# Main.net
KiCad netlist of a schematic drawn in EAGLE
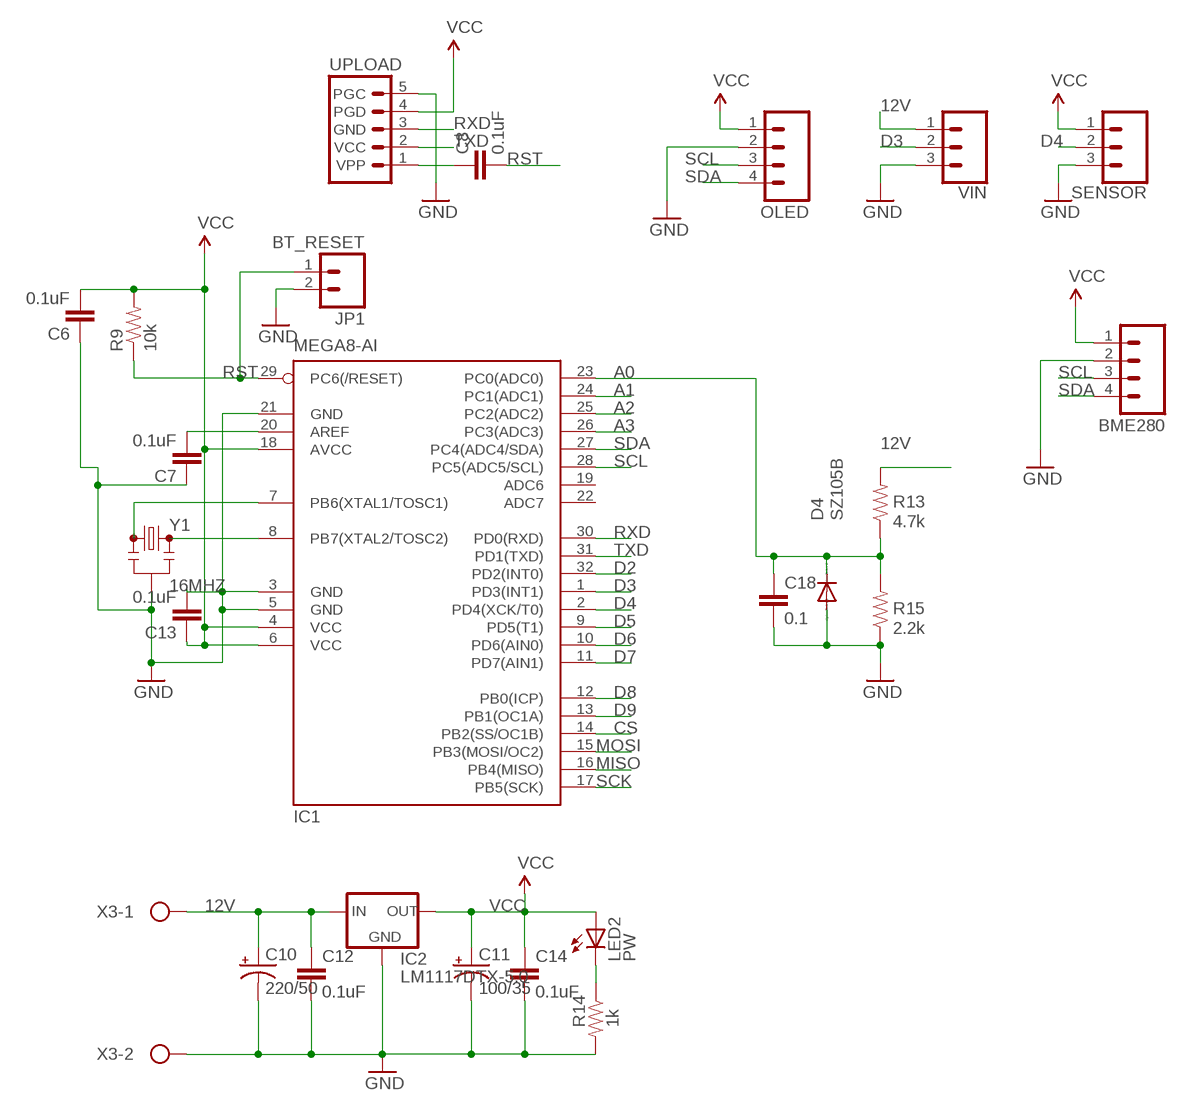
[diagram p0: schematic, sheet 1]

(export (version "E")
  (design (tool "Eeschema 10.0.6"))
  (components
    (comp (ref "BME280")
      (value "M04PTH")
      (footprint "eagle-import:1X04")
      (libsource (lib "eagle-import") (part "M04PTH"))
    )
    (comp (ref "C6")
      (value "0.1uF")
      (footprint "eagle-import:0805")
      (libsource (lib "eagle-import") (part "CAP0805"))
    )
    (comp (ref "C7")
      (value "0.1uF")
      (footprint "eagle-import:0805")
      (libsource (lib "eagle-import") (part "CAP0805"))
    )
    (comp (ref "C8")
      (value "0.1uF")
      (footprint "eagle-import:0805")
      (libsource (lib "eagle-import") (part "CAP0805"))
    )
    (comp (ref "C10")
      (value "220/50")
      (footprint "eagle-import:153CLV-1010")
      (libsource (lib "eagle-import") (part "CPOL-US153CLV-1010"))
    )
    (comp (ref "C11")
      (value "100/35")
      (footprint "eagle-import:153CLV-0605")
      (libsource (lib "eagle-import") (part "CPOL-US153CLV-0605"))
    )
    (comp (ref "C12")
      (value "0.1uF")
      (footprint "eagle-import:0805")
      (libsource (lib "eagle-import") (part "CAP0805"))
    )
    (comp (ref "C13")
      (value "0.1uF")
      (footprint "eagle-import:0805")
      (libsource (lib "eagle-import") (part "CAP0805"))
    )
    (comp (ref "C14")
      (value "0.1uF")
      (footprint "eagle-import:0805")
      (libsource (lib "eagle-import") (part "CAP0805"))
    )
    (comp (ref "C18")
      (value "0.1")
      (footprint "eagle-import:0805")
      (libsource (lib "eagle-import") (part "CAP0805"))
    )
    (comp (ref "D4")
      (value "SZ105B")
      (footprint "eagle-import:DO-214AC")
      (libsource (lib "eagle-import") (part "DIODE-DO-214AC"))
    )
    (comp (ref "IC1")
      (value "MEGA8-AI")
      (footprint "eagle-import:TQFP32-08")
      (fields (field (name "MPN") "ATMEGA8-16AU"))
      (libsource (lib "eagle-import") (part "MEGA8-AI"))
    )
    (comp (ref "IC2")
      (value "LM1117DTX-5.0")
      (footprint "eagle-import:TO252")
      (libsource (lib "eagle-import") (part "LM1117DTX-3.3"))
    )
    (comp (ref "JP1")
      (value "BT_RESET")
      (footprint "eagle-import:1X02")
      (libsource (lib "eagle-import") (part "M02PTH"))
    )
    (comp (ref "LED2")
      (value "PW")
      (footprint "eagle-import:LED3MM")
      (libsource (lib "eagle-import") (part "LED3MM"))
    )
    (comp (ref "OLED")
      (value "M04PTH")
      (footprint "eagle-import:1X04")
      (libsource (lib "eagle-import") (part "M04PTH"))
    )
    (comp (ref "R9")
      (value "10k")
      (footprint "eagle-import:0805")
      (libsource (lib "eagle-import") (part "RESISTOR0805-RES"))
    )
    (comp (ref "R13")
      (value "4.7k")
      (footprint "eagle-import:0805")
      (libsource (lib "eagle-import") (part "RESISTOR0805-RES"))
    )
    (comp (ref "R14")
      (value "1k")
      (footprint "eagle-import:0805")
      (libsource (lib "eagle-import") (part "RESISTOR0805-RES"))
    )
    (comp (ref "R15")
      (value "2.2k")
      (footprint "eagle-import:0805")
      (libsource (lib "eagle-import") (part "RESISTOR0805-RES"))
    )
    (comp (ref "SENSOR")
      (value "CONN_03JST-PTH-VERT")
      (footprint "eagle-import:JST-3-PTH-VERT")
      (libsource (lib "eagle-import") (part "CONN_03JST-PTH-VERT"))
    )
    (comp (ref "UPLOAD")
      (value "PIC_ICSP_MINI_5_PIN")
      (footprint "eagle-import:PIC_ICSP_MINI_5_PIN")
      (libsource (lib "eagle-import") (part "PIC_ICSP_MINI_5_PIN"))
    )
    (comp (ref "VIN")
      (value "CONN_03JST-PTH-VERT")
      (footprint "eagle-import:JST-3-PTH-VERT")
      (libsource (lib "eagle-import") (part "CONN_03JST-PTH-VERT"))
    )
    (comp (ref "X3")
      (value "RELAY1")
      (footprint "eagle-import:W237-102")
      (fields (field (name "MPN") "237-102"))
      (libsource (lib "eagle-import") (part "W237-102"))
    )
    (comp (ref "Y1")
      (value "16MHZ")
      (footprint "eagle-import:RESONATOR-SMD")
      (libsource (lib "eagle-import") (part "RESONATOR16MHZ"))
    )
  )
  (nets
    (net (code "1") (name "/12V") (class "Default")
      (node (ref "C10") (pin "+") (pinfunction "+_+") (pintype "passive"))
      (node (ref "C12") (pin "1") (pinfunction "1_1") (pintype "passive"))
      (node (ref "IC2") (pin "2") (pinfunction "IN_2") (pintype "input"))
      (node (ref "R13") (pin "2") (pinfunction "2_2") (pintype "passive"))
      (node (ref "VIN") (pin "1") (pinfunction "1_1") (pintype "passive"))
      (node (ref "X3") (pin "1") (pinfunction "KL_1") (pintype "passive"))
    )
    (net (code "2") (name "/A0") (class "Default")
      (node (ref "C18") (pin "1") (pinfunction "1_1") (pintype "passive"))
      (node (ref "D4") (pin "C") (pinfunction "C_C") (pintype "passive"))
      (node (ref "IC1") (pin "23") (pinfunction "PC0(ADC0)_23") (pintype "bidirectional"))
      (node (ref "R13") (pin "1") (pinfunction "1_1") (pintype "passive"))
      (node (ref "R15") (pin "2") (pinfunction "2_2") (pintype "passive"))
    )
    (net (code "3") (name "/A1") (class "Default")
      (node (ref "IC1") (pin "24") (pinfunction "PC1(ADC1)_24") (pintype "bidirectional"))
    )
    (net (code "4") (name "/A2") (class "Default")
      (node (ref "IC1") (pin "25") (pinfunction "PC2(ADC2)_25") (pintype "bidirectional"))
    )
    (net (code "5") (name "/A3") (class "Default")
      (node (ref "IC1") (pin "26") (pinfunction "PC3(ADC3)_26") (pintype "bidirectional"))
    )
    (net (code "6") (name "/CS") (class "Default")
      (node (ref "IC1") (pin "14") (pinfunction "PB2(SS/OC1B)_14") (pintype "bidirectional"))
    )
    (net (code "7") (name "/D2") (class "Default")
      (node (ref "IC1") (pin "32") (pinfunction "PD2(INT0)_32") (pintype "bidirectional"))
    )
    (net (code "8") (name "/D3") (class "Default")
      (node (ref "IC1") (pin "1") (pinfunction "PD3(INT1)_1") (pintype "bidirectional"))
      (node (ref "VIN") (pin "2") (pinfunction "2_2") (pintype "passive"))
    )
    (net (code "9") (name "/D4") (class "Default")
      (node (ref "IC1") (pin "2") (pinfunction "PD4(XCK/T0)_2") (pintype "bidirectional"))
      (node (ref "SENSOR") (pin "2") (pinfunction "2_2") (pintype "passive"))
    )
    (net (code "10") (name "/D5") (class "Default")
      (node (ref "IC1") (pin "9") (pinfunction "PD5(T1)_9") (pintype "bidirectional"))
    )
    (net (code "11") (name "/D6") (class "Default")
      (node (ref "IC1") (pin "10") (pinfunction "PD6(AIN0)_10") (pintype "bidirectional"))
    )
    (net (code "12") (name "/D7") (class "Default")
      (node (ref "IC1") (pin "11") (pinfunction "PD7(AIN1)_11") (pintype "bidirectional"))
    )
    (net (code "13") (name "/D8") (class "Default")
      (node (ref "IC1") (pin "12") (pinfunction "PB0(ICP)_12") (pintype "bidirectional"))
    )
    (net (code "14") (name "/D9") (class "Default")
      (node (ref "IC1") (pin "13") (pinfunction "PB1(OC1A)_13") (pintype "bidirectional"))
    )
    (net (code "15") (name "/MISO") (class "Default")
      (node (ref "IC1") (pin "16") (pinfunction "PB4(MISO)_16") (pintype "bidirectional"))
    )
    (net (code "16") (name "/MOSI") (class "Default")
      (node (ref "IC1") (pin "15") (pinfunction "PB3(MOSI/OC2)_15") (pintype "bidirectional"))
    )
    (net (code "17") (name "/RST") (class "Default")
      (node (ref "C8") (pin "2") (pinfunction "2_2") (pintype "passive"))
      (node (ref "IC1") (pin "29") (pinfunction "PC6(/RESET)_29") (pintype "bidirectional"))
      (node (ref "JP1") (pin "1") (pinfunction "1_1") (pintype "passive"))
      (node (ref "R9") (pin "1") (pinfunction "1_1") (pintype "passive"))
    )
    (net (code "18") (name "/RXD") (class "Default")
      (node (ref "IC1") (pin "30") (pinfunction "PD0(RXD)_30") (pintype "bidirectional"))
      (node (ref "UPLOAD") (pin "3") (pinfunction "GND_3") (pintype "passive"))
    )
    (net (code "19") (name "/SCK") (class "Default")
      (node (ref "IC1") (pin "17") (pinfunction "PB5(SCK)_17") (pintype "bidirectional"))
    )
    (net (code "20") (name "/SCL") (class "Default")
      (node (ref "BME280") (pin "3") (pinfunction "3_3") (pintype "passive"))
      (node (ref "IC1") (pin "28") (pinfunction "PC5(ADC5/SCL)_28") (pintype "bidirectional"))
      (node (ref "OLED") (pin "3") (pinfunction "3_3") (pintype "passive"))
    )
    (net (code "21") (name "/SDA") (class "Default")
      (node (ref "BME280") (pin "4") (pinfunction "4_4") (pintype "passive"))
      (node (ref "IC1") (pin "27") (pinfunction "PC4(ADC4/SDA)_27") (pintype "bidirectional"))
      (node (ref "OLED") (pin "4") (pinfunction "4_4") (pintype "passive"))
    )
    (net (code "22") (name "/TXD") (class "Default")
      (node (ref "IC1") (pin "31") (pinfunction "PD1(TXD)_31") (pintype "bidirectional"))
      (node (ref "UPLOAD") (pin "2") (pinfunction "VCC_2") (pintype "passive"))
    )
    (net (code "23") (name "GND") (class "Default")
      (node (ref "BME280") (pin "2") (pinfunction "2_2") (pintype "passive"))
      (node (ref "C10") (pin "-") (pinfunction "-_-") (pintype "passive"))
      (node (ref "C11") (pin "-") (pinfunction "-_-") (pintype "passive"))
      (node (ref "C12") (pin "2") (pinfunction "2_2") (pintype "passive"))
      (node (ref "C13") (pin "2") (pinfunction "2_2") (pintype "passive"))
      (node (ref "C14") (pin "2") (pinfunction "2_2") (pintype "passive"))
      (node (ref "C18") (pin "2") (pinfunction "2_2") (pintype "passive"))
      (node (ref "C6") (pin "1") (pinfunction "1_1") (pintype "passive"))
      (node (ref "C7") (pin "1") (pinfunction "1_1") (pintype "passive"))
      (node (ref "D4") (pin "A") (pinfunction "A_A") (pintype "passive"))
      (node (ref "IC1") (pin "21") (pinfunction "GND_21") (pintype "power_in"))
      (node (ref "IC1") (pin "3") (pinfunction "GND_3") (pintype "power_in"))
      (node (ref "IC1") (pin "5") (pinfunction "GND_5") (pintype "power_in"))
      (node (ref "IC2") (pin "1") (pinfunction "GND_1") (pintype "input"))
      (node (ref "JP1") (pin "2") (pinfunction "2_2") (pintype "passive"))
      (node (ref "OLED") (pin "2") (pinfunction "2_2") (pintype "passive"))
      (node (ref "R14") (pin "2") (pinfunction "2_2") (pintype "passive"))
      (node (ref "R15") (pin "1") (pinfunction "1_1") (pintype "passive"))
      (node (ref "SENSOR") (pin "3") (pinfunction "3_3") (pintype "passive"))
      (node (ref "UPLOAD") (pin "5") (pinfunction "PGC_5") (pintype "passive"))
      (node (ref "VIN") (pin "3") (pinfunction "3_3") (pintype "passive"))
      (node (ref "X3") (pin "2") (pinfunction "KL_2") (pintype "passive"))
      (node (ref "Y1") (pin "2") (pinfunction "2_2") (pintype "passive"))
    )
    (net (code "24") (name "Net-(IC1-AREF)") (class "Default")
      (node (ref "C7") (pin "2") (pinfunction "2_2") (pintype "passive"))
      (node (ref "IC1") (pin "20") (pinfunction "AREF_20") (pintype "passive"))
    )
    (net (code "25") (name "Net-(IC1-PB6(XTAL1{slash}TOSC1))") (class "Default")
      (node (ref "IC1") (pin "7") (pinfunction "PB6(XTAL1/TOSC1)_7") (pintype "bidirectional"))
      (node (ref "Y1") (pin "1") (pinfunction "1_1") (pintype "passive"))
    )
    (net (code "26") (name "Net-(IC1-PB7(XTAL2{slash}TOSC2))") (class "Default")
      (node (ref "IC1") (pin "8") (pinfunction "PB7(XTAL2/TOSC2)_8") (pintype "bidirectional"))
      (node (ref "Y1") (pin "3") (pinfunction "3_3") (pintype "passive"))
    )
    (net (code "27") (name "Net-(LED2-C)") (class "Default")
      (node (ref "LED2") (pin "K") (pinfunction "C_K") (pintype "passive"))
      (node (ref "R14") (pin "1") (pinfunction "1_1") (pintype "passive"))
    )
    (net (code "28") (name "Net-(UPLOAD-VPP)") (class "Default")
      (node (ref "C8") (pin "1") (pinfunction "1_1") (pintype "passive"))
      (node (ref "UPLOAD") (pin "1") (pinfunction "VPP_1") (pintype "passive"))
    )
    (net (code "29") (name "VCC") (class "Default")
      (node (ref "BME280") (pin "1") (pinfunction "1_1") (pintype "passive"))
      (node (ref "C11") (pin "+") (pinfunction "+_+") (pintype "passive"))
      (node (ref "C13") (pin "1") (pinfunction "1_1") (pintype "passive"))
      (node (ref "C14") (pin "1") (pinfunction "1_1") (pintype "passive"))
      (node (ref "C6") (pin "2") (pinfunction "2_2") (pintype "passive"))
      (node (ref "IC1") (pin "18") (pinfunction "AVCC_18") (pintype "power_in"))
      (node (ref "IC1") (pin "4") (pinfunction "VCC_4") (pintype "power_in"))
      (node (ref "IC1") (pin "6") (pinfunction "VCC_6") (pintype "power_in"))
      (node (ref "IC2") (pin "TAB") (pinfunction "OUT_TAB") (pintype "passive"))
      (node (ref "LED2") (pin "A") (pinfunction "A_A") (pintype "passive"))
      (node (ref "OLED") (pin "1") (pinfunction "1_1") (pintype "passive"))
      (node (ref "R9") (pin "2") (pinfunction "2_2") (pintype "passive"))
      (node (ref "SENSOR") (pin "1") (pinfunction "1_1") (pintype "passive"))
      (node (ref "UPLOAD") (pin "4") (pinfunction "PGD_4") (pintype "passive"))
    )
    (net (code "30") (name "unconnected-(IC1-ADC6-Pad19)") (class "Default")
      (node (ref "IC1") (pin "19") (pinfunction "ADC6_19") (pintype "bidirectional"))
    )
    (net (code "31") (name "unconnected-(IC1-ADC7-Pad22)") (class "Default")
      (node (ref "IC1") (pin "22") (pinfunction "ADC7_22") (pintype "bidirectional"))
    )
  )
)
